# alarm_clock_devkit_inputs.net
KiCad netlist of a schematic drawn in Altium Designer
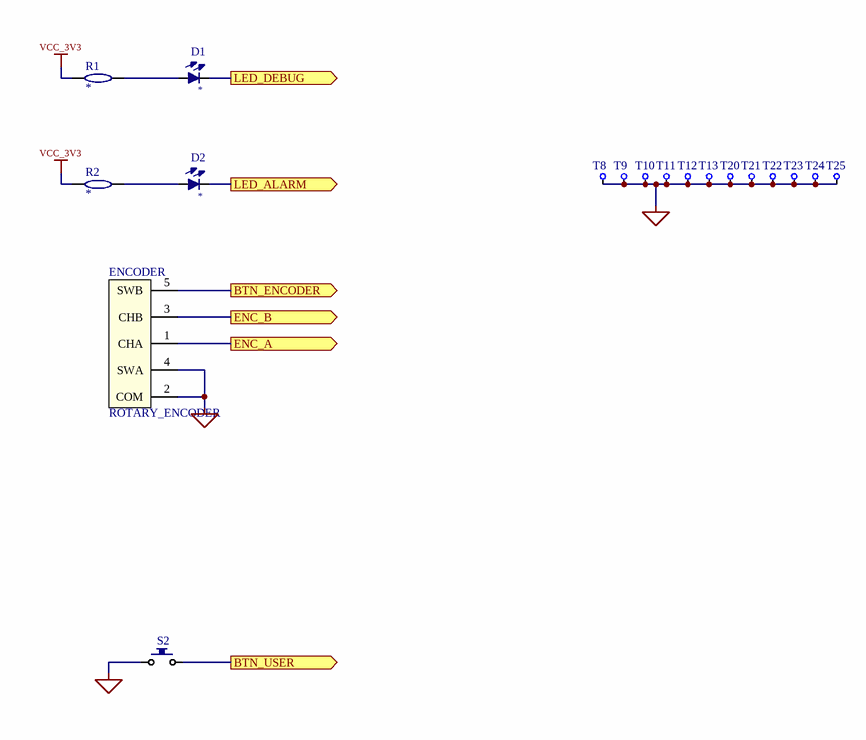
[diagram p0: alarm_clock_devkit_inputs.SchDoc]

(export (version "E")
  (design (tool "Eeschema 10.0.6"))
  (components
    (comp (ref "D1")
      (value "*")
      (footprint "SMT_LED 0603_RED")
      (description "LED")
      (libsource (lib "wifi_alarm_clock") (part "LED"))
    )
    (comp (ref "D2")
      (value "*")
      (footprint "SMT_LED 0603_RED")
      (description "LED")
      (libsource (lib "wifi_alarm_clock") (part "LED"))
    )
    (comp (ref "ENCODER")
      (value "ROTARY_ENCODER")
      (footprint "ENCODER")
      (description "Rotary Encoder")
      (libsource (lib "wifi_alarm_clock") (part "ROTARY_ENCODER"))
    )
    (comp (ref "R1")
      (value "*")
      (footprint "RES 0603_1608")
      (description "Resistor")
      (libsource (lib "wifi_alarm_clock") (part "RESISTOR"))
    )
    (comp (ref "R2")
      (value "*")
      (footprint "RES 0603_1608")
      (description "Resistor")
      (libsource (lib "wifi_alarm_clock") (part "RESISTOR"))
    )
    (comp (ref "S2")
      (value "4-1437565-1")
      (footprint "FSM-SWITCH")
      (description "6x6mm tactile switch SPST_NO")
      (fields (field (name "RS PART NUMBER") "1616046"))
      (libsource (lib "wifi_alarm_clock") (part "BUTTON"))
    )
    (comp (ref "T8")
      (value "TESTPOINT")
      (footprint "TESTPOINT_TH")
      (libsource (lib "wifi_alarm_clock") (part "TESTPOINT"))
    )
    (comp (ref "T9")
      (value "TESTPOINT")
      (footprint "TESTPOINT_TH")
      (libsource (lib "wifi_alarm_clock") (part "TESTPOINT"))
    )
    (comp (ref "T10")
      (value "TESTPOINT")
      (footprint "TESTPOINT_TH")
      (libsource (lib "wifi_alarm_clock") (part "TESTPOINT"))
    )
    (comp (ref "T11")
      (value "TESTPOINT")
      (footprint "TESTPOINT_TH")
      (libsource (lib "wifi_alarm_clock") (part "TESTPOINT"))
    )
    (comp (ref "T12")
      (value "TESTPOINT")
      (footprint "TESTPOINT_TH")
      (libsource (lib "wifi_alarm_clock") (part "TESTPOINT"))
    )
    (comp (ref "T13")
      (value "TESTPOINT")
      (footprint "TESTPOINT_TH")
      (libsource (lib "wifi_alarm_clock") (part "TESTPOINT"))
    )
    (comp (ref "T20")
      (value "TESTPOINT")
      (footprint "TESTPOINT_TH")
      (libsource (lib "wifi_alarm_clock") (part "TESTPOINT"))
    )
    (comp (ref "T21")
      (value "TESTPOINT")
      (footprint "TESTPOINT_TH")
      (libsource (lib "wifi_alarm_clock") (part "TESTPOINT"))
    )
    (comp (ref "T22")
      (value "TESTPOINT")
      (footprint "TESTPOINT_TH")
      (libsource (lib "wifi_alarm_clock") (part "TESTPOINT"))
    )
    (comp (ref "T23")
      (value "TESTPOINT")
      (footprint "TESTPOINT_TH")
      (libsource (lib "wifi_alarm_clock") (part "TESTPOINT"))
    )
    (comp (ref "T24")
      (value "TESTPOINT")
      (footprint "TESTPOINT_TH")
      (libsource (lib "wifi_alarm_clock") (part "TESTPOINT"))
    )
    (comp (ref "T25")
      (value "TESTPOINT")
      (footprint "TESTPOINT_TH")
      (libsource (lib "wifi_alarm_clock") (part "TESTPOINT"))
    )
  )
  (nets
    (net (code "1") (name "/BTN_ENCODER") (class "Default")
      (node (ref "ENCODER") (pin "5") (pinfunction "SWB_5") (pintype "passive"))
    )
    (net (code "2") (name "/BTN_USER") (class "Default")
      (node (ref "S2") (pin "2") (pinfunction "2_2") (pintype "passive"))
    )
    (net (code "3") (name "/ENC_A") (class "Default")
      (node (ref "ENCODER") (pin "1") (pinfunction "CHA_1") (pintype "passive"))
    )
    (net (code "4") (name "/ENC_B") (class "Default")
      (node (ref "ENCODER") (pin "3") (pinfunction "CHB_3") (pintype "passive"))
    )
    (net (code "5") (name "/LED_ALARM") (class "Default")
      (node (ref "D2") (pin "2") (pinfunction "CATHODE_2") (pintype "passive"))
    )
    (net (code "6") (name "/LED_DEBUG") (class "Default")
      (node (ref "D1") (pin "2") (pinfunction "CATHODE_2") (pintype "passive"))
    )
    (net (code "7") (name "GND") (class "Default")
      (node (ref "ENCODER") (pin "2") (pinfunction "COM_2") (pintype "passive"))
      (node (ref "ENCODER") (pin "4") (pinfunction "SWA_4") (pintype "passive"))
      (node (ref "S2") (pin "1") (pinfunction "1_1") (pintype "passive"))
      (node (ref "T10") (pin "1") (pintype "passive"))
      (node (ref "T11") (pin "1") (pintype "passive"))
      (node (ref "T12") (pin "1") (pintype "passive"))
      (node (ref "T13") (pin "1") (pintype "passive"))
      (node (ref "T20") (pin "1") (pintype "passive"))
      (node (ref "T21") (pin "1") (pintype "passive"))
      (node (ref "T22") (pin "1") (pintype "passive"))
      (node (ref "T23") (pin "1") (pintype "passive"))
      (node (ref "T24") (pin "1") (pintype "passive"))
      (node (ref "T25") (pin "1") (pintype "passive"))
      (node (ref "T8") (pin "1") (pintype "passive"))
      (node (ref "T9") (pin "1") (pintype "passive"))
    )
    (net (code "8") (name "Net-(D1-ANODE)") (class "Default")
      (node (ref "D1") (pin "1") (pinfunction "ANODE_1") (pintype "passive"))
      (node (ref "R1") (pin "2") (pinfunction "B_2") (pintype "passive"))
    )
    (net (code "9") (name "Net-(D2-ANODE)") (class "Default")
      (node (ref "D2") (pin "1") (pinfunction "ANODE_1") (pintype "passive"))
      (node (ref "R2") (pin "2") (pinfunction "B_2") (pintype "passive"))
    )
    (net (code "10") (name "VCC_3V3") (class "Default")
      (node (ref "R1") (pin "1") (pinfunction "A_1") (pintype "passive"))
      (node (ref "R2") (pin "1") (pinfunction "A_1") (pintype "passive"))
    )
  )
)
